# DC-DC_Converter_Module_V2.net
KiCad netlist of a schematic drawn in EAGLE
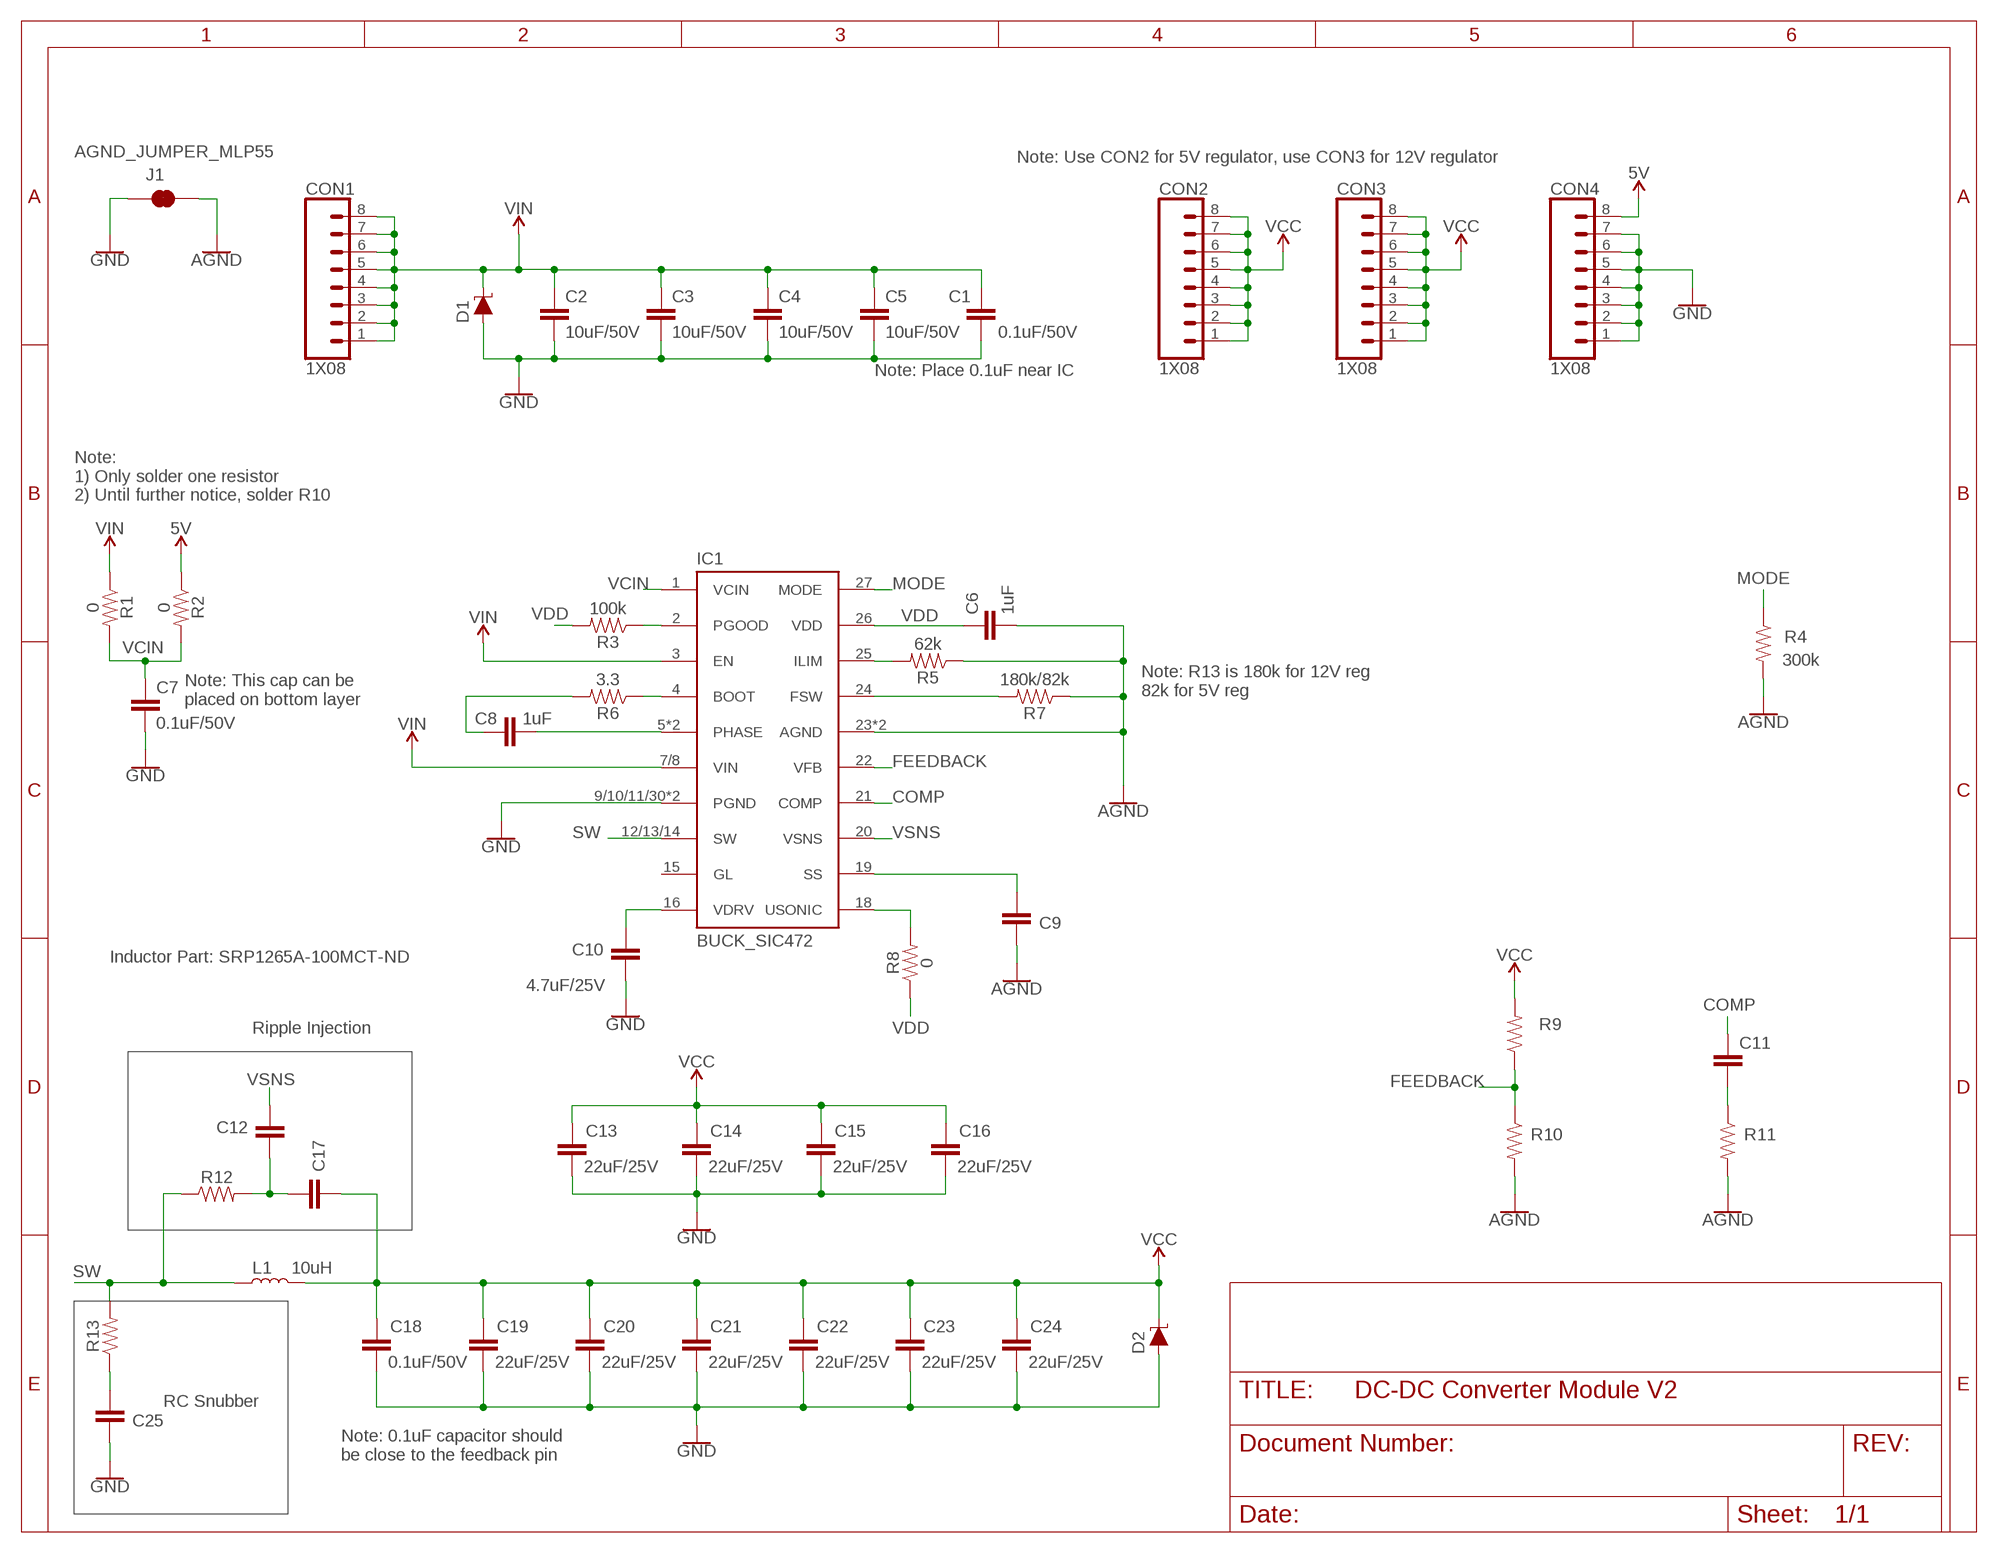
[diagram p0: schematic, sheet 1]

(export (version "E")
  (design (tool "Eeschema 10.0.6"))
  (components
    (comp (ref "C1")
      (value "0.1uF/50V")
      (footprint "eagle-import:0805")
      (libsource (lib "eagle-import") (part "CAPACITOR_0805"))
    )
    (comp (ref "C2")
      (value "10uF/50V")
      (footprint "eagle-import:1210")
      (libsource (lib "eagle-import") (part "CAPACITOR_1210"))
    )
    (comp (ref "C3")
      (value "10uF/50V")
      (footprint "eagle-import:1210")
      (libsource (lib "eagle-import") (part "CAPACITOR_1210"))
    )
    (comp (ref "C4")
      (value "10uF/50V")
      (footprint "eagle-import:1210")
      (libsource (lib "eagle-import") (part "CAPACITOR_1210"))
    )
    (comp (ref "C5")
      (value "10uF/50V")
      (footprint "eagle-import:1210")
      (libsource (lib "eagle-import") (part "CAPACITOR_1210"))
    )
    (comp (ref "C6")
      (value "1uF")
      (footprint "eagle-import:0805")
      (libsource (lib "eagle-import") (part "CAPACITOR_0805"))
    )
    (comp (ref "C7")
      (value "0.1uF/50V")
      (footprint "eagle-import:0805")
      (libsource (lib "eagle-import") (part "CAPACITOR_0805"))
    )
    (comp (ref "C8")
      (value "1uF")
      (footprint "eagle-import:0805")
      (libsource (lib "eagle-import") (part "CAPACITOR_0805"))
    )
    (comp (ref "C9")
      (value "CAPACITOR_0805")
      (footprint "eagle-import:0805")
      (libsource (lib "eagle-import") (part "CAPACITOR_0805"))
    )
    (comp (ref "C10")
      (value "4.7uF/25V")
      (footprint "eagle-import:0805")
      (libsource (lib "eagle-import") (part "CAPACITOR_0805"))
    )
    (comp (ref "C11")
      (value "CAPACITOR_0805")
      (footprint "eagle-import:0805")
      (libsource (lib "eagle-import") (part "CAPACITOR_0805"))
    )
    (comp (ref "C12")
      (value "CAPACITOR_0805")
      (footprint "eagle-import:0805")
      (libsource (lib "eagle-import") (part "CAPACITOR_0805"))
    )
    (comp (ref "C13")
      (value "22uF/25V")
      (footprint "eagle-import:0805")
      (libsource (lib "eagle-import") (part "CAPACITOR_0805"))
    )
    (comp (ref "C14")
      (value "22uF/25V")
      (footprint "eagle-import:0805")
      (libsource (lib "eagle-import") (part "CAPACITOR_0805"))
    )
    (comp (ref "C15")
      (value "22uF/25V")
      (footprint "eagle-import:0805")
      (libsource (lib "eagle-import") (part "CAPACITOR_0805"))
    )
    (comp (ref "C16")
      (value "22uF/25V")
      (footprint "eagle-import:0805")
      (libsource (lib "eagle-import") (part "CAPACITOR_0805"))
    )
    (comp (ref "C17")
      (value "CAPACITOR_0805")
      (footprint "eagle-import:0805")
      (libsource (lib "eagle-import") (part "CAPACITOR_0805"))
    )
    (comp (ref "C18")
      (value "0.1uF/50V")
      (footprint "eagle-import:0805")
      (libsource (lib "eagle-import") (part "CAPACITOR_0805"))
    )
    (comp (ref "C19")
      (value "22uF/25V")
      (footprint "eagle-import:0805")
      (libsource (lib "eagle-import") (part "CAPACITOR_0805"))
    )
    (comp (ref "C20")
      (value "22uF/25V")
      (footprint "eagle-import:0805")
      (libsource (lib "eagle-import") (part "CAPACITOR_0805"))
    )
    (comp (ref "C21")
      (value "22uF/25V")
      (footprint "eagle-import:0805")
      (libsource (lib "eagle-import") (part "CAPACITOR_0805"))
    )
    (comp (ref "C22")
      (value "22uF/25V")
      (footprint "eagle-import:0805")
      (libsource (lib "eagle-import") (part "CAPACITOR_0805"))
    )
    (comp (ref "C23")
      (value "22uF/25V")
      (footprint "eagle-import:0805")
      (libsource (lib "eagle-import") (part "CAPACITOR_0805"))
    )
    (comp (ref "C24")
      (value "22uF/25V")
      (footprint "eagle-import:0805")
      (libsource (lib "eagle-import") (part "CAPACITOR_0805"))
    )
    (comp (ref "C25")
      (value "CAPACITOR_0805")
      (footprint "eagle-import:0805")
      (libsource (lib "eagle-import") (part "CAPACITOR_0805"))
    )
    (comp (ref "CON1")
      (value "1X08")
      (footprint "eagle-import:1X08")
      (libsource (lib "eagle-import") (part "1X08"))
    )
    (comp (ref "CON2")
      (value "1X08")
      (footprint "eagle-import:1X08")
      (libsource (lib "eagle-import") (part "1X08"))
    )
    (comp (ref "CON3")
      (value "1X08")
      (footprint "eagle-import:1X08")
      (libsource (lib "eagle-import") (part "1X08"))
    )
    (comp (ref "CON4")
      (value "1X08")
      (footprint "eagle-import:1X08")
      (libsource (lib "eagle-import") (part "1X08"))
    )
    (comp (ref "D1")
      (value "DIODE_TVS_DO-214AA")
      (footprint "eagle-import:DO214AA")
      (libsource (lib "eagle-import") (part "DIODE_TVS_DO-214AA"))
    )
    (comp (ref "D2")
      (value "DIODE_TVS_DO-214AA")
      (footprint "eagle-import:DO214AA")
      (libsource (lib "eagle-import") (part "DIODE_TVS_DO-214AA"))
    )
    (comp (ref "IC1")
      (value "BUCK_SIC472")
      (footprint "eagle-import:MLP55-27L")
      (libsource (lib "eagle-import") (part "BUCK_SIC472"))
    )
    (comp (ref "J1")
      (value "AGND_JUMPER_MLP55")
      (footprint "eagle-import:AGND_JUMPER_MLP55")
      (libsource (lib "eagle-import") (part "AGND_JUMPER_MLP55"))
    )
    (comp (ref "L1")
      (value "10uH")
      (footprint "eagle-import:INDUCTOR_BOURNS_SRP1265A")
      (libsource (lib "eagle-import") (part "INDUCTOR_BOURNS_SRP1265A"))
    )
    (comp (ref "R1")
      (value "0")
      (footprint "eagle-import:0805")
      (libsource (lib "eagle-import") (part "RESISTOR_0805"))
    )
    (comp (ref "R2")
      (value "0")
      (footprint "eagle-import:0805")
      (libsource (lib "eagle-import") (part "RESISTOR_0805"))
    )
    (comp (ref "R3")
      (value "100k")
      (footprint "eagle-import:0805")
      (libsource (lib "eagle-import") (part "RESISTOR_0805"))
    )
    (comp (ref "R4")
      (value "300k")
      (footprint "eagle-import:0805")
      (libsource (lib "eagle-import") (part "RESISTOR_0805"))
    )
    (comp (ref "R5")
      (value "62k")
      (footprint "eagle-import:0805")
      (libsource (lib "eagle-import") (part "RESISTOR_0805"))
    )
    (comp (ref "R6")
      (value "3.3")
      (footprint "eagle-import:0805")
      (libsource (lib "eagle-import") (part "RESISTOR_0805"))
    )
    (comp (ref "R7")
      (value "180k/82k")
      (footprint "eagle-import:0805")
      (libsource (lib "eagle-import") (part "RESISTOR_0805"))
    )
    (comp (ref "R8")
      (value "0")
      (footprint "eagle-import:0805")
      (libsource (lib "eagle-import") (part "RESISTOR_0805"))
    )
    (comp (ref "R9")
      (value "RESISTOR_0805")
      (footprint "eagle-import:0805")
      (libsource (lib "eagle-import") (part "RESISTOR_0805"))
    )
    (comp (ref "R10")
      (value "RESISTOR_0805")
      (footprint "eagle-import:0805")
      (libsource (lib "eagle-import") (part "RESISTOR_0805"))
    )
    (comp (ref "R11")
      (value "RESISTOR_0805")
      (footprint "eagle-import:0805")
      (libsource (lib "eagle-import") (part "RESISTOR_0805"))
    )
    (comp (ref "R12")
      (value "RESISTOR_0805")
      (footprint "eagle-import:0805")
      (libsource (lib "eagle-import") (part "RESISTOR_0805"))
    )
    (comp (ref "R13")
      (value "RESISTOR_0805")
      (footprint "eagle-import:0805")
      (libsource (lib "eagle-import") (part "RESISTOR_0805"))
    )
  )
  (nets
    (net (code "1") (name "/COMP") (class "Default")
      (node (ref "C11") (pin "2") (pinfunction "2_2") (pintype "passive"))
      (node (ref "IC1") (pin "21") (pinfunction "COMP_21") (pintype "bidirectional"))
    )
    (net (code "2") (name "/FEEDBACK") (class "Default")
      (node (ref "IC1") (pin "22") (pinfunction "VFB_22") (pintype "bidirectional"))
      (node (ref "R10") (pin "1") (pinfunction "1_1") (pintype "passive"))
      (node (ref "R9") (pin "1") (pinfunction "1_1") (pintype "passive"))
    )
    (net (code "3") (name "/MODE") (class "Default")
      (node (ref "IC1") (pin "27") (pinfunction "MODE_27") (pintype "bidirectional"))
      (node (ref "R4") (pin "1") (pinfunction "1_1") (pintype "passive"))
    )
    (net (code "4") (name "/SW") (class "Default")
      (node (ref "IC1") (pin "12/13/14") (pinfunction "SW_12/13/14") (pintype "bidirectional"))
      (node (ref "L1") (pin "1") (pinfunction "1_1") (pintype "passive"))
      (node (ref "R12") (pin "1") (pinfunction "1_1") (pintype "passive"))
      (node (ref "R13") (pin "2") (pinfunction "2_2") (pintype "passive"))
    )
    (net (code "5") (name "/VCIN") (class "Default")
      (node (ref "C7") (pin "1") (pinfunction "1_1") (pintype "passive"))
      (node (ref "IC1") (pin "1") (pinfunction "VCIN_1") (pintype "bidirectional"))
      (node (ref "R1") (pin "2") (pinfunction "2_2") (pintype "passive"))
      (node (ref "R2") (pin "2") (pinfunction "2_2") (pintype "passive"))
    )
    (net (code "6") (name "/VDD") (class "Default")
      (node (ref "C6") (pin "1") (pinfunction "1_1") (pintype "passive"))
      (node (ref "IC1") (pin "26") (pinfunction "VDD_26") (pintype "bidirectional"))
      (node (ref "R3") (pin "2") (pinfunction "2_2") (pintype "passive"))
      (node (ref "R8") (pin "1") (pinfunction "1_1") (pintype "passive"))
    )
    (net (code "7") (name "/VSNS") (class "Default")
      (node (ref "C12") (pin "1") (pinfunction "1_1") (pintype "passive"))
      (node (ref "IC1") (pin "20") (pinfunction "VSNS_20") (pintype "bidirectional"))
    )
    (net (code "8") (name "5V") (class "Default")
      (node (ref "CON4") (pin "8") (pinfunction "8_8") (pintype "passive"))
      (node (ref "R2") (pin "1") (pinfunction "1_1") (pintype "passive"))
    )
    (net (code "9") (name "AGND") (class "Default")
      (node (ref "C6") (pin "2") (pinfunction "2_2") (pintype "passive"))
      (node (ref "C9") (pin "1") (pinfunction "1_1") (pintype "passive"))
      (node (ref "IC1") (pin "23") (pinfunction "AGND_23") (pintype "bidirectional"))
      (node (ref "IC1") (pin "28") (pinfunction "AGND_28") (pintype "bidirectional"))
      (node (ref "J1") (pin "P$2") (pinfunction "2_P$2") (pintype "passive"))
      (node (ref "R10") (pin "2") (pinfunction "2_2") (pintype "passive"))
      (node (ref "R11") (pin "2") (pinfunction "2_2") (pintype "passive"))
      (node (ref "R4") (pin "2") (pinfunction "2_2") (pintype "passive"))
      (node (ref "R5") (pin "1") (pinfunction "1_1") (pintype "passive"))
      (node (ref "R7") (pin "1") (pinfunction "1_1") (pintype "passive"))
    )
    (net (code "10") (name "GND") (class "Default")
      (node (ref "C1") (pin "1") (pinfunction "1_1") (pintype "passive"))
      (node (ref "C10") (pin "2") (pinfunction "2_2") (pintype "passive"))
      (node (ref "C13") (pin "1") (pinfunction "1_1") (pintype "passive"))
      (node (ref "C14") (pin "1") (pinfunction "1_1") (pintype "passive"))
      (node (ref "C15") (pin "1") (pinfunction "1_1") (pintype "passive"))
      (node (ref "C16") (pin "1") (pinfunction "1_1") (pintype "passive"))
      (node (ref "C18") (pin "1") (pinfunction "1_1") (pintype "passive"))
      (node (ref "C19") (pin "1") (pinfunction "1_1") (pintype "passive"))
      (node (ref "C2") (pin "2") (pinfunction "2_2") (pintype "passive"))
      (node (ref "C20") (pin "1") (pinfunction "1_1") (pintype "passive"))
      (node (ref "C21") (pin "1") (pinfunction "1_1") (pintype "passive"))
      (node (ref "C22") (pin "1") (pinfunction "1_1") (pintype "passive"))
      (node (ref "C23") (pin "1") (pinfunction "1_1") (pintype "passive"))
      (node (ref "C24") (pin "1") (pinfunction "1_1") (pintype "passive"))
      (node (ref "C25") (pin "1") (pinfunction "1_1") (pintype "passive"))
      (node (ref "C3") (pin "2") (pinfunction "2_2") (pintype "passive"))
      (node (ref "C4") (pin "2") (pinfunction "2_2") (pintype "passive"))
      (node (ref "C5") (pin "2") (pinfunction "2_2") (pintype "passive"))
      (node (ref "C7") (pin "2") (pinfunction "2_2") (pintype "passive"))
      (node (ref "CON4") (pin "1") (pinfunction "1_1") (pintype "passive"))
      (node (ref "CON4") (pin "2") (pinfunction "2_2") (pintype "passive"))
      (node (ref "CON4") (pin "3") (pinfunction "3_3") (pintype "passive"))
      (node (ref "CON4") (pin "4") (pinfunction "4_4") (pintype "passive"))
      (node (ref "CON4") (pin "5") (pinfunction "5_5") (pintype "passive"))
      (node (ref "CON4") (pin "6") (pinfunction "6_6") (pintype "passive"))
      (node (ref "CON4") (pin "7") (pinfunction "7_7") (pintype "passive"))
      (node (ref "D1") (pin "A") (pinfunction "A_A") (pintype "passive"))
      (node (ref "D2") (pin "A") (pinfunction "A_A") (pintype "passive"))
      (node (ref "IC1") (pin "17") (pinfunction "PGND_17") (pintype "bidirectional"))
      (node (ref "IC1") (pin "9/10/11/30") (pinfunction "PGND_9/10/11/30") (pintype "bidirectional"))
      (node (ref "J1") (pin "P$1") (pinfunction "1_P$1") (pintype "passive"))
    )
    (net (code "11") (name "Net-(C8-Pad1)") (class "Default")
      (node (ref "C8") (pin "1") (pinfunction "1_1") (pintype "passive"))
      (node (ref "R6") (pin "2") (pinfunction "2_2") (pintype "passive"))
    )
    (net (code "12") (name "Net-(C8-Pad2)") (class "Default")
      (node (ref "C8") (pin "2") (pinfunction "2_2") (pintype "passive"))
      (node (ref "IC1") (pin "5") (pinfunction "PHASE_5") (pintype "bidirectional"))
      (node (ref "IC1") (pin "6") (pinfunction "PHASE_6") (pintype "bidirectional"))
    )
    (net (code "13") (name "Net-(C11-Pad1)") (class "Default")
      (node (ref "C11") (pin "1") (pinfunction "1_1") (pintype "passive"))
      (node (ref "R11") (pin "1") (pinfunction "1_1") (pintype "passive"))
    )
    (net (code "14") (name "Net-(C12-Pad2)") (class "Default")
      (node (ref "C12") (pin "2") (pinfunction "2_2") (pintype "passive"))
      (node (ref "C17") (pin "2") (pinfunction "2_2") (pintype "passive"))
      (node (ref "R12") (pin "2") (pinfunction "2_2") (pintype "passive"))
    )
    (net (code "15") (name "Net-(C25-Pad2)") (class "Default")
      (node (ref "C25") (pin "2") (pinfunction "2_2") (pintype "passive"))
      (node (ref "R13") (pin "1") (pinfunction "1_1") (pintype "passive"))
    )
    (net (code "16") (name "Net-(IC1-BOOT)") (class "Default")
      (node (ref "IC1") (pin "4") (pinfunction "BOOT_4") (pintype "bidirectional"))
      (node (ref "R6") (pin "1") (pinfunction "1_1") (pintype "passive"))
    )
    (net (code "17") (name "Net-(IC1-FSW)") (class "Default")
      (node (ref "IC1") (pin "24") (pinfunction "FSW_24") (pintype "bidirectional"))
      (node (ref "R7") (pin "2") (pinfunction "2_2") (pintype "passive"))
    )
    (net (code "18") (name "Net-(IC1-ILIM)") (class "Default")
      (node (ref "IC1") (pin "25") (pinfunction "ILIM_25") (pintype "bidirectional"))
      (node (ref "R5") (pin "2") (pinfunction "2_2") (pintype "passive"))
    )
    (net (code "19") (name "Net-(IC1-PGOOD)") (class "Default")
      (node (ref "IC1") (pin "2") (pinfunction "PGOOD_2") (pintype "bidirectional"))
      (node (ref "R3") (pin "1") (pinfunction "1_1") (pintype "passive"))
    )
    (net (code "20") (name "Net-(IC1-SS)") (class "Default")
      (node (ref "C9") (pin "2") (pinfunction "2_2") (pintype "passive"))
      (node (ref "IC1") (pin "19") (pinfunction "SS_19") (pintype "bidirectional"))
    )
    (net (code "21") (name "Net-(IC1-USONIC)") (class "Default")
      (node (ref "IC1") (pin "18") (pinfunction "USONIC_18") (pintype "bidirectional"))
      (node (ref "R8") (pin "2") (pinfunction "2_2") (pintype "passive"))
    )
    (net (code "22") (name "Net-(IC1-VDRV)") (class "Default")
      (node (ref "C10") (pin "1") (pinfunction "1_1") (pintype "passive"))
      (node (ref "IC1") (pin "16") (pinfunction "VDRV_16") (pintype "bidirectional"))
    )
    (net (code "23") (name "VCC") (class "Default")
      (node (ref "C13") (pin "2") (pinfunction "2_2") (pintype "passive"))
      (node (ref "C14") (pin "2") (pinfunction "2_2") (pintype "passive"))
      (node (ref "C15") (pin "2") (pinfunction "2_2") (pintype "passive"))
      (node (ref "C16") (pin "2") (pinfunction "2_2") (pintype "passive"))
      (node (ref "C17") (pin "1") (pinfunction "1_1") (pintype "passive"))
      (node (ref "C18") (pin "2") (pinfunction "2_2") (pintype "passive"))
      (node (ref "C19") (pin "2") (pinfunction "2_2") (pintype "passive"))
      (node (ref "C20") (pin "2") (pinfunction "2_2") (pintype "passive"))
      (node (ref "C21") (pin "2") (pinfunction "2_2") (pintype "passive"))
      (node (ref "C22") (pin "2") (pinfunction "2_2") (pintype "passive"))
      (node (ref "C23") (pin "2") (pinfunction "2_2") (pintype "passive"))
      (node (ref "C24") (pin "2") (pinfunction "2_2") (pintype "passive"))
      (node (ref "CON2") (pin "1") (pinfunction "1_1") (pintype "passive"))
      (node (ref "CON2") (pin "2") (pinfunction "2_2") (pintype "passive"))
      (node (ref "CON2") (pin "3") (pinfunction "3_3") (pintype "passive"))
      (node (ref "CON2") (pin "4") (pinfunction "4_4") (pintype "passive"))
      (node (ref "CON2") (pin "5") (pinfunction "5_5") (pintype "passive"))
      (node (ref "CON2") (pin "6") (pinfunction "6_6") (pintype "passive"))
      (node (ref "CON2") (pin "7") (pinfunction "7_7") (pintype "passive"))
      (node (ref "CON2") (pin "8") (pinfunction "8_8") (pintype "passive"))
      (node (ref "CON3") (pin "1") (pinfunction "1_1") (pintype "passive"))
      (node (ref "CON3") (pin "2") (pinfunction "2_2") (pintype "passive"))
      (node (ref "CON3") (pin "3") (pinfunction "3_3") (pintype "passive"))
      (node (ref "CON3") (pin "4") (pinfunction "4_4") (pintype "passive"))
      (node (ref "CON3") (pin "5") (pinfunction "5_5") (pintype "passive"))
      (node (ref "CON3") (pin "6") (pinfunction "6_6") (pintype "passive"))
      (node (ref "CON3") (pin "7") (pinfunction "7_7") (pintype "passive"))
      (node (ref "CON3") (pin "8") (pinfunction "8_8") (pintype "passive"))
      (node (ref "D2") (pin "C") (pinfunction "C_C") (pintype "passive"))
      (node (ref "L1") (pin "2") (pinfunction "2_2") (pintype "passive"))
      (node (ref "R9") (pin "2") (pinfunction "2_2") (pintype "passive"))
    )
    (net (code "24") (name "VIN") (class "Default")
      (node (ref "C1") (pin "2") (pinfunction "2_2") (pintype "passive"))
      (node (ref "C2") (pin "1") (pinfunction "1_1") (pintype "passive"))
      (node (ref "C3") (pin "1") (pinfunction "1_1") (pintype "passive"))
      (node (ref "C4") (pin "1") (pinfunction "1_1") (pintype "passive"))
      (node (ref "C5") (pin "1") (pinfunction "1_1") (pintype "passive"))
      (node (ref "CON1") (pin "1") (pinfunction "1_1") (pintype "passive"))
      (node (ref "CON1") (pin "2") (pinfunction "2_2") (pintype "passive"))
      (node (ref "CON1") (pin "3") (pinfunction "3_3") (pintype "passive"))
      (node (ref "CON1") (pin "4") (pinfunction "4_4") (pintype "passive"))
      (node (ref "CON1") (pin "5") (pinfunction "5_5") (pintype "passive"))
      (node (ref "CON1") (pin "6") (pinfunction "6_6") (pintype "passive"))
      (node (ref "CON1") (pin "7") (pinfunction "7_7") (pintype "passive"))
      (node (ref "CON1") (pin "8") (pinfunction "8_8") (pintype "passive"))
      (node (ref "D1") (pin "C") (pinfunction "C_C") (pintype "passive"))
      (node (ref "IC1") (pin "3") (pinfunction "EN_3") (pintype "bidirectional"))
      (node (ref "IC1") (pin "7/8") (pinfunction "VIN_7/8") (pintype "bidirectional"))
      (node (ref "R1") (pin "1") (pinfunction "1_1") (pintype "passive"))
    )
    (net (code "25") (name "unconnected-(IC1-GL-Pad15)") (class "Default")
      (node (ref "IC1") (pin "15") (pinfunction "GL_15") (pintype "bidirectional"))
    )
  )
)
